# Pr_tica-02.net
KiCad netlist of a schematic drawn in EasyEDA
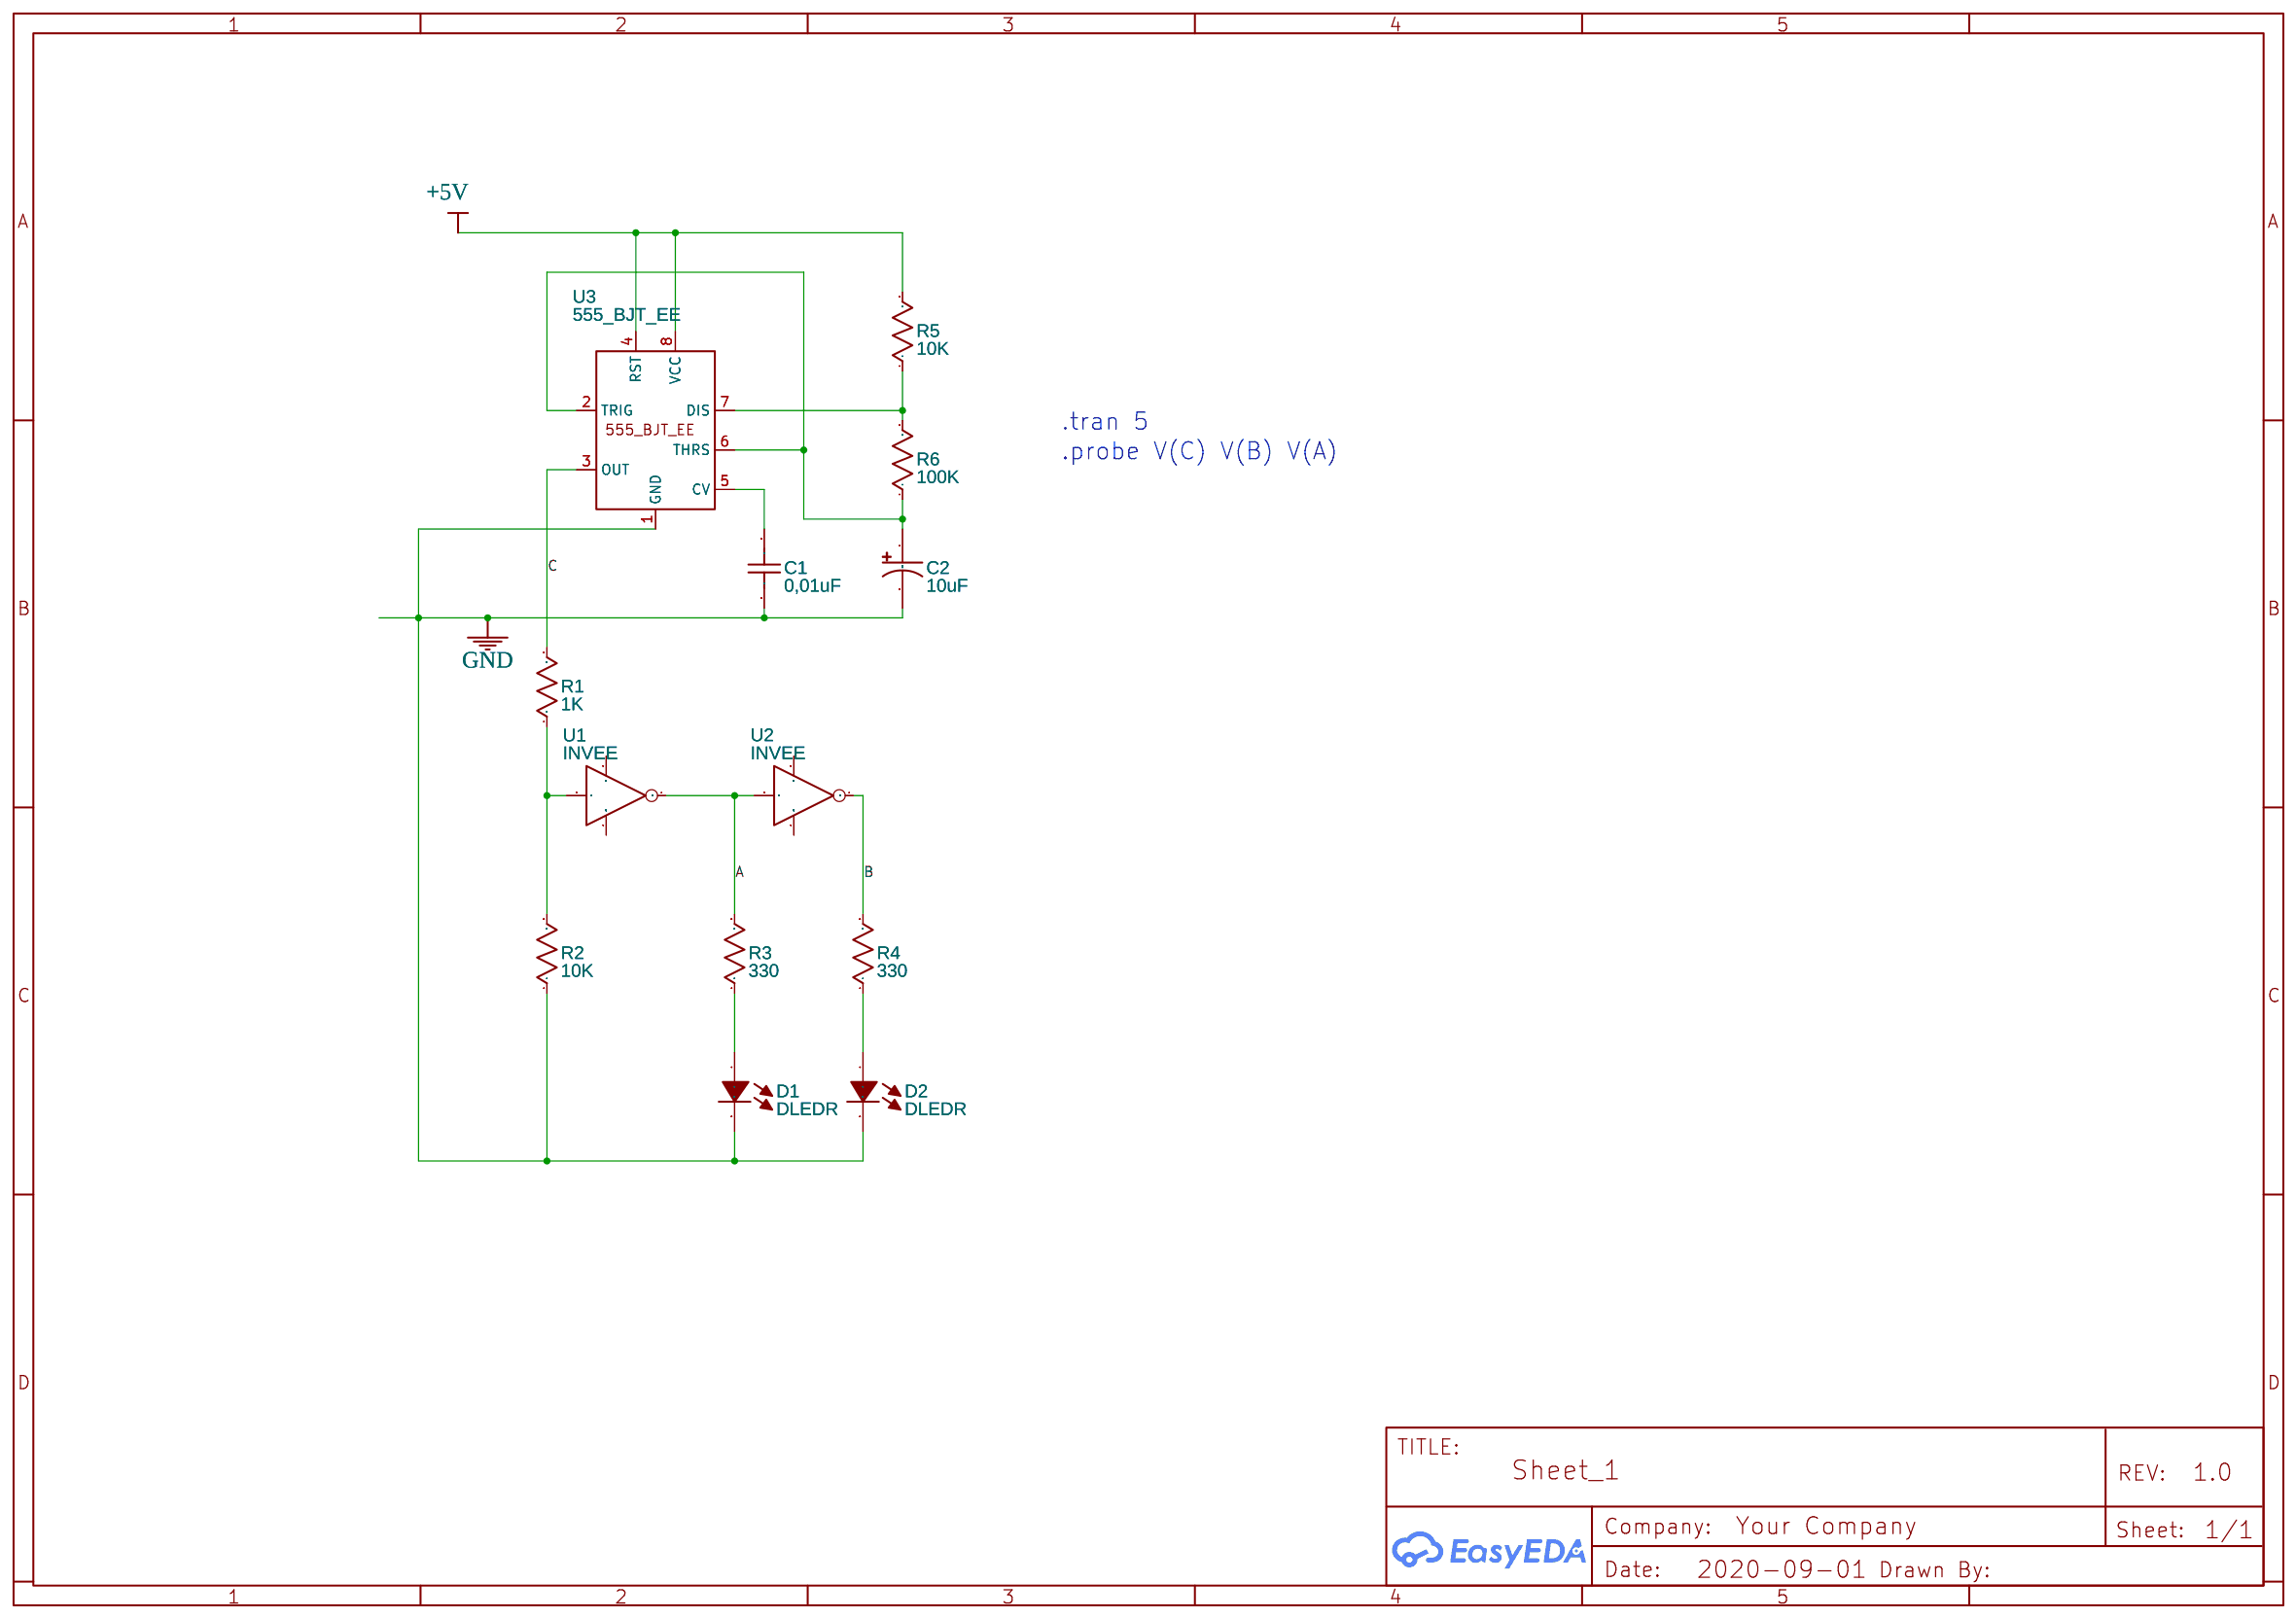
[diagram p0: schematic sheet]

(export (version "E")
  (design (tool "Eeschema 10.0.6"))
  (components
    (comp (ref "C1") (value "0,01uF") (libsource (lib "") (part "Capacitor_US")))
    (comp (ref "C2") (value "10uF") (libsource (lib "") (part "Capacitor_Electrolytic_US")))
    (comp (ref "D1") (value "DLEDR") (libsource (lib "") (part "DLEDR")))
    (comp (ref "D2") (value "DLEDR") (libsource (lib "") (part "DLEDR")))
    (comp (ref "R1") (value "1K") (libsource (lib "") (part "Resistor_US")))
    (comp (ref "R2") (value "10K") (libsource (lib "") (part "Resistor_US")))
    (comp (ref "R3") (value "330") (libsource (lib "") (part "Resistor_US")))
    (comp (ref "R4") (value "330") (libsource (lib "") (part "Resistor_US")))
    (comp (ref "R5") (value "10K") (libsource (lib "") (part "Resistor_US")))
    (comp (ref "R6") (value "100K") (libsource (lib "") (part "Resistor_US")))
    (comp (ref "U1") (value "INVEE") (libsource (lib "") (part "LOGIC")))
    (comp (ref "U2") (value "INVEE") (libsource (lib "") (part "LOGIC")))
    (comp (ref "U3") (value "555_BJT_EE") (libsource (lib "") (part "555_BJT_EE")))
  )
  (nets
    (net (code "1") (name "+5V") (class "Default")
      (node (ref "R5") (pin "2") (pinfunction "2_2") (pintype "unspecified"))
      (node (ref "U3") (pin "4") (pinfunction "RST_4") (pintype "unspecified"))
      (node (ref "U3") (pin "8") (pinfunction "VCC_8") (pintype "unspecified"))
    )
    (net (code "2") (name "/A") (class "Default")
      (node (ref "R3") (pin "2") (pinfunction "2_2") (pintype "unspecified"))
      (node (ref "U1") (pin "4") (pinfunction "OUT_4") (pintype "output"))
      (node (ref "U2") (pin "1") (pinfunction "IN_1") (pintype "input"))
    )
    (net (code "3") (name "/B") (class "Default")
      (node (ref "R4") (pin "2") (pinfunction "2_2") (pintype "unspecified"))
      (node (ref "U2") (pin "4") (pinfunction "OUT_4") (pintype "output"))
    )
    (net (code "4") (name "/C") (class "Default")
      (node (ref "R1") (pin "2") (pinfunction "2_2") (pintype "unspecified"))
      (node (ref "U3") (pin "3") (pinfunction "OUT_3") (pintype "unspecified"))
    )
    (net (code "5") (name "GND") (class "Default")
      (node (ref "C1") (pin "1") (pinfunction "1_1") (pintype "unspecified"))
      (node (ref "C2") (pin "2") (pinfunction "2_2") (pintype "unspecified"))
      (node (ref "D1") (pin "2") (pinfunction "C_2") (pintype "unspecified"))
      (node (ref "D2") (pin "2") (pinfunction "C_2") (pintype "unspecified"))
      (node (ref "R2") (pin "1") (pinfunction "1_1") (pintype "unspecified"))
      (node (ref "U3") (pin "1") (pinfunction "GND_1") (pintype "unspecified"))
    )
    (net (code "6") (name "Net-(D1-A)") (class "Default")
      (node (ref "D1") (pin "1") (pinfunction "A_1") (pintype "unspecified"))
      (node (ref "R3") (pin "1") (pinfunction "1_1") (pintype "unspecified"))
    )
    (net (code "7") (name "Net-(D2-A)") (class "Default")
      (node (ref "D2") (pin "1") (pinfunction "A_1") (pintype "unspecified"))
      (node (ref "R4") (pin "1") (pinfunction "1_1") (pintype "unspecified"))
    )
    (net (code "8") (name "Net-(U1-IN)") (class "Default")
      (node (ref "R1") (pin "1") (pinfunction "1_1") (pintype "unspecified"))
      (node (ref "R2") (pin "2") (pinfunction "2_2") (pintype "unspecified"))
      (node (ref "U1") (pin "1") (pinfunction "IN_1") (pintype "input"))
    )
    (net (code "9") (name "Net-(U3-CV)") (class "Default")
      (node (ref "C1") (pin "2") (pinfunction "2_2") (pintype "unspecified"))
      (node (ref "U3") (pin "5") (pinfunction "CV_5") (pintype "unspecified"))
    )
    (net (code "10") (name "Net-(U3-DIS)") (class "Default")
      (node (ref "R5") (pin "1") (pinfunction "1_1") (pintype "unspecified"))
      (node (ref "R6") (pin "2") (pinfunction "2_2") (pintype "unspecified"))
      (node (ref "U3") (pin "7") (pinfunction "DIS_7") (pintype "unspecified"))
    )
    (net (code "11") (name "Net-(U3-THRS)") (class "Default")
      (node (ref "C2") (pin "1") (pinfunction "1_1") (pintype "unspecified"))
      (node (ref "R6") (pin "1") (pinfunction "1_1") (pintype "unspecified"))
      (node (ref "U3") (pin "2") (pinfunction "TRIG_2") (pintype "unspecified"))
      (node (ref "U3") (pin "6") (pinfunction "THRS_6") (pintype "unspecified"))
    )
    (net (code "12") (name "unconnected-(U1-GND-Pad3)") (class "Default")
      (node (ref "U1") (pin "3") (pinfunction "GND_3") (pintype "passive"))
    )
    (net (code "13") (name "unconnected-(U1-VDD-Pad2)") (class "Default")
      (node (ref "U1") (pin "2") (pinfunction "VDD_2") (pintype "passive"))
    )
    (net (code "14") (name "unconnected-(U2-GND-Pad3)") (class "Default")
      (node (ref "U2") (pin "3") (pinfunction "GND_3") (pintype "passive"))
    )
    (net (code "15") (name "unconnected-(U2-VDD-Pad2)") (class "Default")
      (node (ref "U2") (pin "2") (pinfunction "VDD_2") (pintype "passive"))
    )
  )
)
